# Sheet3.net
KiCad netlist of a schematic drawn in Altium Designer
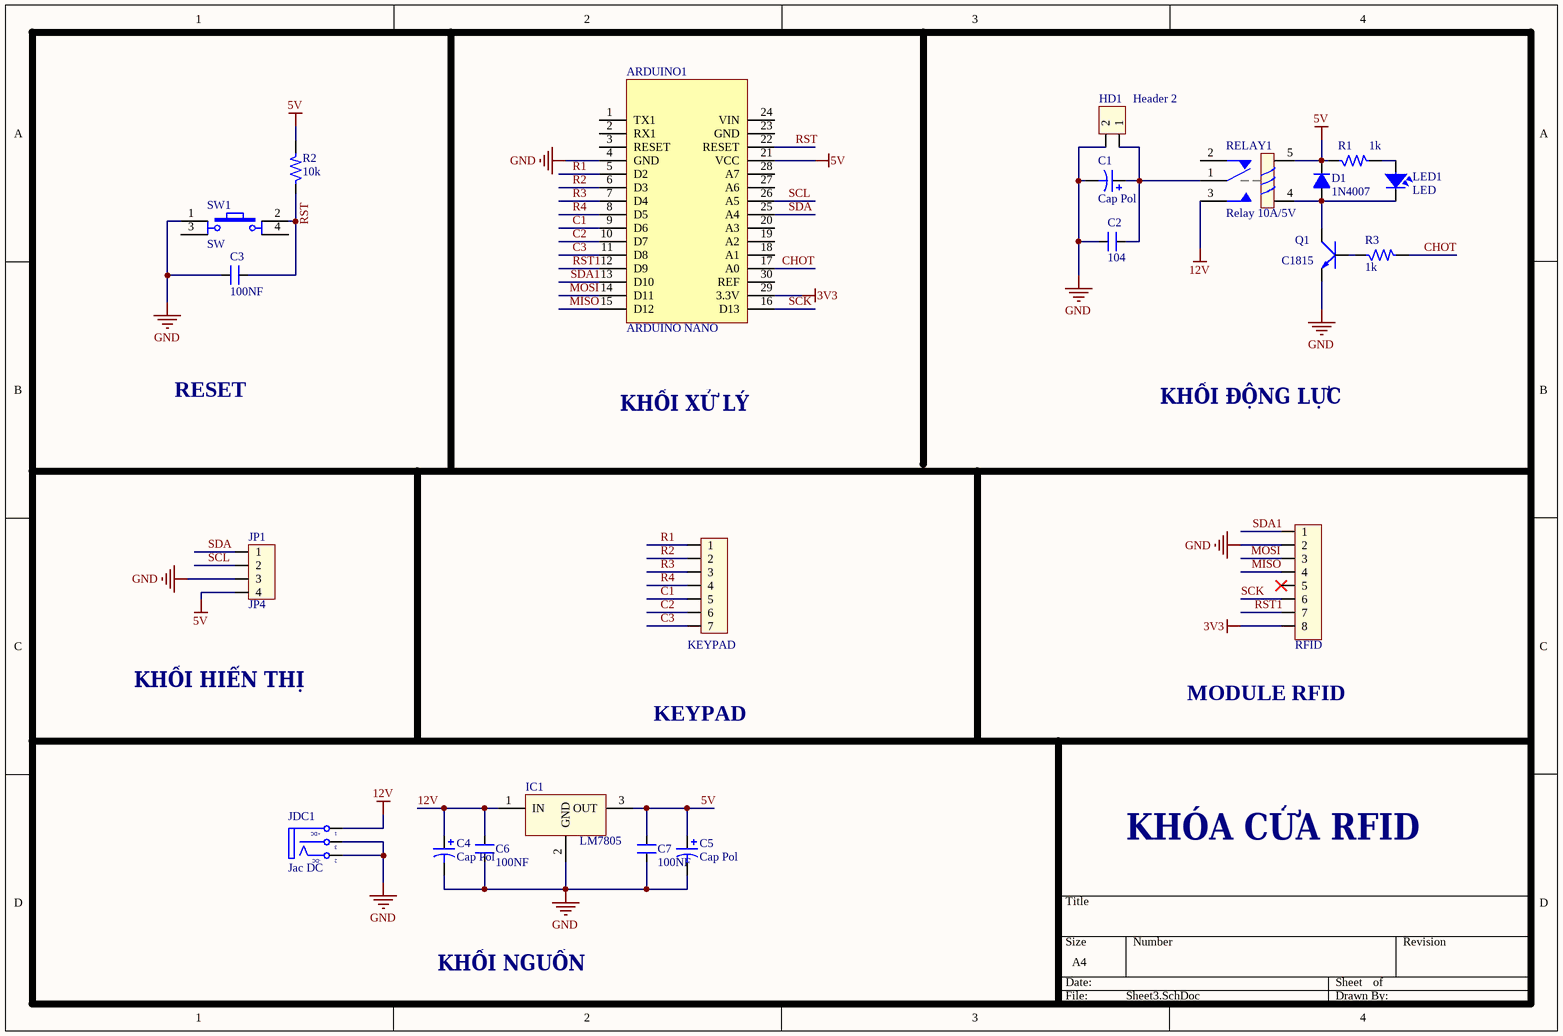
[diagram p0: Sheet3.SchDoc]

(export (version "E")
  (design (tool "Eeschema 10.0.6"))
  (components
    (comp (ref "ARDUINO1")
      (value "ARDUINO NANO")
      (footprint "ARDUINO PRO NANO")
      (libsource (lib "My library altium") (part "ARDUINO NANO"))
    )
    (comp (ref "C1")
      (value "Cap Pol")
      (footprint "C3MM")
      (description "Polarized Capacitor (Axial)")
      (fields (field (name "PUBLISHER") "Altium Limited"))
      (libsource (lib "My library altium") (part "Cap Pol"))
    )
    (comp (ref "C2")
      (value "104")
      (footprint "CN1")
      (description "Cap np  1pF - 472pF")
      (libsource (lib "syhaunguyen") (part "CN1"))
    )
    (comp (ref "C3")
      (value "100NF")
      (footprint "CN1")
      (description "Cap np  1pF - 472pF")
      (libsource (lib "syhaunguyen") (part "CN1"))
    )
    (comp (ref "C4")
      (value "Cap Pol")
      (footprint "C3MM")
      (description "Polarized Capacitor (Axial)")
      (fields (field (name "PUBLISHER") "Altium Limited"))
      (libsource (lib "My library altium") (part "Cap Pol"))
    )
    (comp (ref "C5")
      (value "Cap Pol")
      (footprint "C3MM")
      (description "Polarized Capacitor (Axial)")
      (fields (field (name "PUBLISHER") "Altium Limited"))
      (libsource (lib "My library altium") (part "Cap Pol"))
    )
    (comp (ref "C6")
      (value "100NF")
      (footprint "CN1")
      (description "Cap np  1pF - 472pF")
      (libsource (lib "syhaunguyen") (part "CN1"))
    )
    (comp (ref "C7")
      (value "100NF")
      (footprint "CN1")
      (description "Cap np  1pF - 472pF")
      (libsource (lib "syhaunguyen") (part "CN1"))
    )
    (comp (ref "D1")
      (value "1N4007")
      (footprint "D1A")
      (description "Diode 1A")
      (libsource (lib "syhaunguyen") (part "D1A"))
    )
    (comp (ref "H1")
      (value "RFID")
      (footprint "XH2.54M-8")
      (description "Cắm")
      (libsource (lib "Altium_Lib_by_KhueNguyenCreator") (part "Header 8P 2.54 Duc Thang"))
    )
    (comp (ref "H2")
      (value "KEYPAD")
      (footprint "XH2.54M-7")
      (description "Cắm")
      (libsource (lib "Altium_Lib_by_KhueNguyenCreator") (part "Header 7P 2.54 Duc Thang"))
    )
    (comp (ref "HD1")
      (value "Header 2")
      (footprint "HED2")
      (description "Header 2 (Green)")
      (libsource (lib "syhaunguyen") (part "Hed2"))
    )
    (comp (ref "IC1")
      (value "LM7805")
      (footprint "QTO-220")
      (description "On ap +, from + 5 to + 24VDC")
      (libsource (lib "syhaunguyen") (part "LM78xx"))
    )
    (comp (ref "JDC1")
      (value "Jac DC")
      (footprint "DC-IN")
      (description "Jac DC input")
      (libsource (lib "syhaunguyen") (part "DCIN"))
    )
    (comp (ref "JP1")
      (value "JP4")
      (footprint "HuanHaui_FEETEAM:CON4")
      (description "Connector 4")
      (libsource (lib "HuanHaui_FEETEAM") (part "Con4"))
    )
    (comp (ref "LED1")
      (value "LED")
      (footprint "LED-3")
      (description "LED Single colour Green and Red")
      (libsource (lib "syhaunguyen") (part "LED"))
    )
    (comp (ref "Q1")
      (value "C1815")
      (footprint "QTO-92")
      (description "NPN 600mW, ECB")
      (libsource (lib "syhaunguyen") (part "C1815"))
    )
    (comp (ref "R1")
      (value "1k")
      (footprint "RES-1/4W")
      (description "Resistor 1/4W")
      (libsource (lib "syhaunguyen") (part "R"))
    )
    (comp (ref "R2")
      (value "10k")
      (footprint "RES-1/4W")
      (description "Resistor 1/4W")
      (libsource (lib "syhaunguyen") (part "R"))
    )
    (comp (ref "R3")
      (value "1k")
      (footprint "RES-1/4W")
      (description "Resistor 1/4W")
      (libsource (lib "syhaunguyen") (part "R"))
    )
    (comp (ref "RELAY1")
      (value "Relay 10A/5V")
      (footprint "HuanHaui_FEETEAM:RL_SPDT_10A - duplicate")
      (description "Relay SPDT,10A - 12VDC 5 Pin")
      (libsource (lib "HuanHaui_FEETEAM") (part "Relay 1"))
    )
    (comp (ref "SW1")
      (value "SW")
      (footprint "SW4")
      (description "Switch button 4 pin")
      (libsource (lib "syhaunguyen") (part "SW4"))
    )
  )
  (nets
    (net (code "1") (name "/C1") (class "Default")
      (node (ref "ARDUINO1") (pin "9") (pinfunction "D6_9") (pintype "passive"))
      (node (ref "H2") (pin "5") (pinfunction "5_5") (pintype "passive"))
    )
    (net (code "2") (name "/C2") (class "Default")
      (node (ref "ARDUINO1") (pin "10") (pinfunction "D7_10") (pintype "passive"))
      (node (ref "H2") (pin "6") (pinfunction "6_6") (pintype "passive"))
    )
    (net (code "3") (name "/C3") (class "Default")
      (node (ref "ARDUINO1") (pin "11") (pinfunction "D8_11") (pintype "passive"))
      (node (ref "H2") (pin "7") (pinfunction "7_7") (pintype "passive"))
    )
    (net (code "4") (name "/CHOT") (class "Default")
      (node (ref "ARDUINO1") (pin "17") (pinfunction "A0_17") (pintype "passive"))
      (node (ref "R3") (pin "2") (pinfunction "2_2") (pintype "passive"))
    )
    (net (code "5") (name "/MISO") (class "Default")
      (node (ref "ARDUINO1") (pin "15") (pinfunction "D12_15") (pintype "passive"))
      (node (ref "H1") (pin "4") (pinfunction "4_4") (pintype "passive"))
    )
    (net (code "6") (name "/MOSI") (class "Default")
      (node (ref "ARDUINO1") (pin "14") (pinfunction "D11_14") (pintype "passive"))
      (node (ref "H1") (pin "3") (pinfunction "3_3") (pintype "passive"))
    )
    (net (code "7") (name "/R1") (class "Default")
      (node (ref "ARDUINO1") (pin "5") (pinfunction "D2_5") (pintype "passive"))
      (node (ref "H2") (pin "1") (pinfunction "1_1") (pintype "passive"))
    )
    (net (code "8") (name "/R2") (class "Default")
      (node (ref "ARDUINO1") (pin "6") (pinfunction "D3_6") (pintype "passive"))
      (node (ref "H2") (pin "2") (pinfunction "2_2") (pintype "passive"))
    )
    (net (code "9") (name "/R3") (class "Default")
      (node (ref "ARDUINO1") (pin "7") (pinfunction "D4_7") (pintype "passive"))
      (node (ref "H2") (pin "3") (pinfunction "3_3") (pintype "passive"))
    )
    (net (code "10") (name "/R4") (class "Default")
      (node (ref "ARDUINO1") (pin "8") (pinfunction "D5_8") (pintype "passive"))
      (node (ref "H2") (pin "4") (pinfunction "4_4") (pintype "passive"))
    )
    (net (code "11") (name "/RST") (class "Default")
      (node (ref "ARDUINO1") (pin "22") (pinfunction "RESET_22") (pintype "passive"))
      (node (ref "C3") (pin "2") (pinfunction "2_2") (pintype "passive"))
      (node (ref "R2") (pin "1") (pinfunction "1_1") (pintype "passive"))
      (node (ref "SW1") (pin "2") (pintype "passive"))
    )
    (net (code "12") (name "/RST1") (class "Default")
      (node (ref "ARDUINO1") (pin "12") (pinfunction "D9_12") (pintype "passive"))
      (node (ref "H1") (pin "7") (pinfunction "7_7") (pintype "passive"))
    )
    (net (code "13") (name "/SCK") (class "Default")
      (node (ref "ARDUINO1") (pin "16") (pinfunction "D13_16") (pintype "passive"))
      (node (ref "H1") (pin "6") (pinfunction "6_6") (pintype "passive"))
    )
    (net (code "14") (name "/SCL") (class "Default")
      (node (ref "ARDUINO1") (pin "26") (pinfunction "A5_26") (pintype "passive"))
      (node (ref "JP1") (pin "2") (pinfunction "2_2") (pintype "passive"))
    )
    (net (code "15") (name "/SDA") (class "Default")
      (node (ref "ARDUINO1") (pin "25") (pinfunction "A4_25") (pintype "passive"))
      (node (ref "JP1") (pin "1") (pinfunction "1_1") (pintype "passive"))
    )
    (net (code "16") (name "/SDA1") (class "Default")
      (node (ref "ARDUINO1") (pin "13") (pinfunction "D10_13") (pintype "passive"))
      (node (ref "H1") (pin "1") (pinfunction "1_1") (pintype "passive"))
    )
    (net (code "17") (name "3V3") (class "Default")
      (node (ref "ARDUINO1") (pin "29") (pinfunction "3.3V_29") (pintype "passive"))
      (node (ref "H1") (pin "8") (pinfunction "8_8") (pintype "passive"))
    )
    (net (code "18") (name "5V") (class "Default")
      (node (ref "ARDUINO1") (pin "21") (pinfunction "VCC_21") (pintype "passive"))
      (node (ref "C5") (pin "1") (pinfunction "1_1") (pintype "passive"))
      (node (ref "C7") (pin "2") (pinfunction "2_2") (pintype "passive"))
      (node (ref "D1") (pin "2") (pinfunction "K_2") (pintype "passive"))
      (node (ref "IC1") (pin "3") (pinfunction "OUT_3") (pintype "passive"))
      (node (ref "JP1") (pin "4") (pinfunction "4_4") (pintype "passive"))
      (node (ref "R1") (pin "1") (pinfunction "1_1") (pintype "passive"))
      (node (ref "R2") (pin "2") (pinfunction "2_2") (pintype "passive"))
      (node (ref "RELAY1") (pin "5") (pinfunction "5_5") (pintype "passive"))
    )
    (net (code "19") (name "12V") (class "Default")
      (node (ref "C4") (pin "1") (pinfunction "1_1") (pintype "passive"))
      (node (ref "C6") (pin "2") (pinfunction "2_2") (pintype "passive"))
      (node (ref "IC1") (pin "1") (pinfunction "IN_1") (pintype "passive"))
      (node (ref "JDC1") (pin "1") (pinfunction "T_1") (pintype "passive"))
      (node (ref "RELAY1") (pin "3") (pinfunction "3_3") (pintype "passive"))
    )
    (net (code "20") (name "GND") (class "Default")
      (node (ref "ARDUINO1") (pin "4") (pinfunction "GND_4") (pintype "passive"))
      (node (ref "C1") (pin "2") (pinfunction "2_2") (pintype "passive"))
      (node (ref "C2") (pin "2") (pinfunction "2_2") (pintype "passive"))
      (node (ref "C3") (pin "1") (pinfunction "1_1") (pintype "passive"))
      (node (ref "C4") (pin "2") (pinfunction "2_2") (pintype "passive"))
      (node (ref "C5") (pin "2") (pinfunction "2_2") (pintype "passive"))
      (node (ref "C6") (pin "1") (pinfunction "1_1") (pintype "passive"))
      (node (ref "C7") (pin "1") (pinfunction "1_1") (pintype "passive"))
      (node (ref "H1") (pin "2") (pinfunction "2_2") (pintype "passive"))
      (node (ref "HD1") (pin "2") (pinfunction "2_2") (pintype "passive"))
      (node (ref "IC1") (pin "2") (pinfunction "GND_2") (pintype "passive"))
      (node (ref "JDC1") (pin "2") (pinfunction "TN_2") (pintype "passive"))
      (node (ref "JDC1") (pin "3") (pinfunction "S_3") (pintype "power_in"))
      (node (ref "JP1") (pin "3") (pinfunction "3_3") (pintype "passive"))
      (node (ref "Q1") (pin "1") (pinfunction "E_1") (pintype "passive"))
      (node (ref "SW1") (pin "1") (pintype "passive"))
    )
    (net (code "21") (name "Net-(C1-Pad1)") (class "Default")
      (node (ref "C1") (pin "1") (pinfunction "1_1") (pintype "passive"))
      (node (ref "C2") (pin "1") (pinfunction "1_1") (pintype "passive"))
      (node (ref "HD1") (pin "1") (pinfunction "1_1") (pintype "passive"))
      (node (ref "RELAY1") (pin "1") (pinfunction "1_1") (pintype "passive"))
    )
    (net (code "22") (name "Net-(D1-A)") (class "Default")
      (node (ref "D1") (pin "1") (pinfunction "A_1") (pintype "passive"))
      (node (ref "LED1") (pin "2") (pinfunction "2_2") (pintype "passive"))
      (node (ref "Q1") (pin "2") (pinfunction "C_2") (pintype "passive"))
      (node (ref "RELAY1") (pin "4") (pinfunction "4_4") (pintype "passive"))
    )
    (net (code "23") (name "Net-(LED1-Pad1)") (class "Default")
      (node (ref "LED1") (pin "1") (pinfunction "1_1") (pintype "passive"))
      (node (ref "R1") (pin "2") (pinfunction "2_2") (pintype "passive"))
    )
    (net (code "24") (name "Net-(Q1-B)") (class "Default")
      (node (ref "Q1") (pin "3") (pinfunction "B_3") (pintype "passive"))
      (node (ref "R3") (pin "1") (pinfunction "1_1") (pintype "passive"))
    )
    (net (code "25") (name "unconnected-(ARDUINO1-A1-Pad18)") (class "Default")
      (node (ref "ARDUINO1") (pin "18") (pinfunction "A1_18") (pintype "passive"))
    )
    (net (code "26") (name "unconnected-(ARDUINO1-A2-Pad19)") (class "Default")
      (node (ref "ARDUINO1") (pin "19") (pinfunction "A2_19") (pintype "passive"))
    )
    (net (code "27") (name "unconnected-(ARDUINO1-A3-Pad20)") (class "Default")
      (node (ref "ARDUINO1") (pin "20") (pinfunction "A3_20") (pintype "passive"))
    )
    (net (code "28") (name "unconnected-(ARDUINO1-A6-Pad27)") (class "Default")
      (node (ref "ARDUINO1") (pin "27") (pinfunction "A6_27") (pintype "passive"))
    )
    (net (code "29") (name "unconnected-(ARDUINO1-A7-Pad28)") (class "Default")
      (node (ref "ARDUINO1") (pin "28") (pinfunction "A7_28") (pintype "passive"))
    )
    (net (code "30") (name "unconnected-(ARDUINO1-GND-Pad23)") (class "Default")
      (node (ref "ARDUINO1") (pin "23") (pinfunction "GND_23") (pintype "passive"))
    )
    (net (code "31") (name "unconnected-(ARDUINO1-REF-Pad30)") (class "Default")
      (node (ref "ARDUINO1") (pin "30") (pinfunction "REF_30") (pintype "passive"))
    )
    (net (code "32") (name "unconnected-(ARDUINO1-RESET-Pad3)") (class "Default")
      (node (ref "ARDUINO1") (pin "3") (pinfunction "RESET_3") (pintype "passive"))
    )
    (net (code "33") (name "unconnected-(ARDUINO1-RX1-Pad2)") (class "Default")
      (node (ref "ARDUINO1") (pin "2") (pinfunction "RX1_2") (pintype "passive"))
    )
    (net (code "34") (name "unconnected-(ARDUINO1-TX1-Pad1)") (class "Default")
      (node (ref "ARDUINO1") (pin "1") (pinfunction "TX1_1") (pintype "passive"))
    )
    (net (code "35") (name "unconnected-(ARDUINO1-VIN-Pad24)") (class "Default")
      (node (ref "ARDUINO1") (pin "24") (pinfunction "VIN_24") (pintype "passive"))
    )
    (net (code "36") (name "unconnected-(H1-Pad5)") (class "Default")
      (node (ref "H1") (pin "5") (pinfunction "5_5") (pintype "passive+no_connect"))
    )
    (net (code "37") (name "unconnected-(RELAY1-Pad2)") (class "Default")
      (node (ref "RELAY1") (pin "2") (pinfunction "2_2") (pintype "passive"))
    )
    (net (code "38") (name "unconnected-(SW1-Pad3)") (class "Default")
      (node (ref "SW1") (pin "3") (pintype "passive"))
    )
    (net (code "39") (name "unconnected-(SW1-Pad4)") (class "Default")
      (node (ref "SW1") (pin "4") (pintype "passive"))
    )
  )
)
